# main3.net
KiCad netlist of a schematic drawn in EAGLE
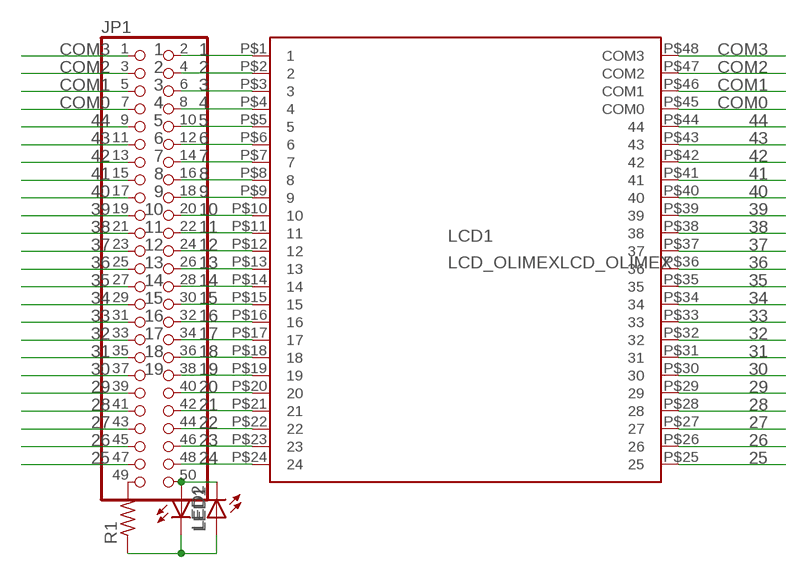
[diagram p0: schematic, sheet 1]

(export (version "E")
  (design (tool "Eeschema 10.0.6"))
  (components
    (comp (ref "JP1")
      (value "PINHD-2X25")
      (footprint "eagle-import:2X25")
      (libsource (lib "eagle-import") (part "PINHD-2X25"))
    )
    (comp (ref "LCD1")
      (value "LCD_OLIMEXLCD_OLIMEX")
      (footprint "eagle-import:LCD_OLIMEX")
      (libsource (lib "eagle-import") (part "LCD_OLIMEXLCD_OLIMEX"))
    )
    (comp (ref "LED1")
      (value "LED_ESML0603")
      (footprint "eagle-import:LED_SML0603")
      (libsource (lib "eagle-import") (part "LED_ESML0603"))
    )
    (comp (ref "LED2")
      (value "LED_ESML0603")
      (footprint "eagle-import:LED_SML0603")
      (libsource (lib "eagle-import") (part "LED_ESML0603"))
    )
    (comp (ref "R1")
      (value "R-US_R0603")
      (footprint "eagle-import:R0603")
      (libsource (lib "eagle-import") (part "R-US_R0603"))
    )
  )
  (nets
    (net (code "1") (name "/1") (class "Default")
      (node (ref "JP1") (pin "2") (pinfunction "2_2") (pintype "passive"))
      (node (ref "LCD1") (pin "P$1") (pinfunction "1_P$1") (pintype "bidirectional"))
    )
    (net (code "2") (name "/2") (class "Default")
      (node (ref "JP1") (pin "4") (pinfunction "4_4") (pintype "passive"))
      (node (ref "LCD1") (pin "P$2") (pinfunction "2_P$2") (pintype "bidirectional"))
    )
    (net (code "3") (name "/3") (class "Default")
      (node (ref "JP1") (pin "6") (pinfunction "6_6") (pintype "passive"))
      (node (ref "LCD1") (pin "P$3") (pinfunction "3_P$3") (pintype "bidirectional"))
    )
    (net (code "4") (name "/4") (class "Default")
      (node (ref "JP1") (pin "8") (pinfunction "8_8") (pintype "passive"))
      (node (ref "LCD1") (pin "P$4") (pinfunction "4_P$4") (pintype "bidirectional"))
    )
    (net (code "5") (name "/5") (class "Default")
      (node (ref "JP1") (pin "10") (pinfunction "10_10") (pintype "passive"))
      (node (ref "LCD1") (pin "P$5") (pinfunction "5_P$5") (pintype "bidirectional"))
    )
    (net (code "6") (name "/6") (class "Default")
      (node (ref "JP1") (pin "12") (pinfunction "12_12") (pintype "passive"))
      (node (ref "LCD1") (pin "P$6") (pinfunction "6_P$6") (pintype "bidirectional"))
    )
    (net (code "7") (name "/7") (class "Default")
      (node (ref "JP1") (pin "14") (pinfunction "14_14") (pintype "passive"))
      (node (ref "LCD1") (pin "P$7") (pinfunction "7_P$7") (pintype "bidirectional"))
    )
    (net (code "8") (name "/8") (class "Default")
      (node (ref "JP1") (pin "16") (pinfunction "16_16") (pintype "passive"))
      (node (ref "LCD1") (pin "P$8") (pinfunction "8_P$8") (pintype "bidirectional"))
    )
    (net (code "9") (name "/9") (class "Default")
      (node (ref "JP1") (pin "18") (pinfunction "18_18") (pintype "passive"))
      (node (ref "LCD1") (pin "P$9") (pinfunction "9_P$9") (pintype "bidirectional"))
    )
    (net (code "10") (name "/10") (class "Default")
      (node (ref "JP1") (pin "20") (pinfunction "20_20") (pintype "passive"))
      (node (ref "LCD1") (pin "P$10") (pinfunction "10_P$10") (pintype "bidirectional"))
    )
    (net (code "11") (name "/11") (class "Default")
      (node (ref "JP1") (pin "22") (pinfunction "22_22") (pintype "passive"))
      (node (ref "LCD1") (pin "P$11") (pinfunction "11_P$11") (pintype "bidirectional"))
    )
    (net (code "12") (name "/12") (class "Default")
      (node (ref "JP1") (pin "24") (pinfunction "24_24") (pintype "passive"))
      (node (ref "LCD1") (pin "P$12") (pinfunction "12_P$12") (pintype "bidirectional"))
    )
    (net (code "13") (name "/13") (class "Default")
      (node (ref "JP1") (pin "26") (pinfunction "26_26") (pintype "passive"))
      (node (ref "LCD1") (pin "P$13") (pinfunction "13_P$13") (pintype "bidirectional"))
    )
    (net (code "14") (name "/14") (class "Default")
      (node (ref "JP1") (pin "28") (pinfunction "28_28") (pintype "passive"))
      (node (ref "LCD1") (pin "P$14") (pinfunction "14_P$14") (pintype "bidirectional"))
    )
    (net (code "15") (name "/15") (class "Default")
      (node (ref "JP1") (pin "30") (pinfunction "30_30") (pintype "passive"))
      (node (ref "LCD1") (pin "P$15") (pinfunction "15_P$15") (pintype "bidirectional"))
    )
    (net (code "16") (name "/16") (class "Default")
      (node (ref "JP1") (pin "32") (pinfunction "32_32") (pintype "passive"))
      (node (ref "LCD1") (pin "P$16") (pinfunction "16_P$16") (pintype "bidirectional"))
    )
    (net (code "17") (name "/17") (class "Default")
      (node (ref "JP1") (pin "34") (pinfunction "34_34") (pintype "passive"))
      (node (ref "LCD1") (pin "P$17") (pinfunction "17_P$17") (pintype "bidirectional"))
    )
    (net (code "18") (name "/18") (class "Default")
      (node (ref "JP1") (pin "36") (pinfunction "36_36") (pintype "passive"))
      (node (ref "LCD1") (pin "P$18") (pinfunction "18_P$18") (pintype "bidirectional"))
    )
    (net (code "19") (name "/19") (class "Default")
      (node (ref "JP1") (pin "38") (pinfunction "38_38") (pintype "passive"))
      (node (ref "LCD1") (pin "P$19") (pinfunction "19_P$19") (pintype "bidirectional"))
    )
    (net (code "20") (name "/20") (class "Default")
      (node (ref "JP1") (pin "40") (pinfunction "40_40") (pintype "passive"))
      (node (ref "LCD1") (pin "P$20") (pinfunction "20_P$20") (pintype "bidirectional"))
    )
    (net (code "21") (name "/21") (class "Default")
      (node (ref "JP1") (pin "42") (pinfunction "42_42") (pintype "passive"))
      (node (ref "LCD1") (pin "P$21") (pinfunction "21_P$21") (pintype "bidirectional"))
    )
    (net (code "22") (name "/22") (class "Default")
      (node (ref "JP1") (pin "44") (pinfunction "44_44") (pintype "passive"))
      (node (ref "LCD1") (pin "P$22") (pinfunction "22_P$22") (pintype "bidirectional"))
    )
    (net (code "23") (name "/23") (class "Default")
      (node (ref "JP1") (pin "46") (pinfunction "46_46") (pintype "passive"))
      (node (ref "LCD1") (pin "P$23") (pinfunction "23_P$23") (pintype "bidirectional"))
    )
    (net (code "24") (name "/24") (class "Default")
      (node (ref "JP1") (pin "48") (pinfunction "48_48") (pintype "passive"))
      (node (ref "LCD1") (pin "P$24") (pinfunction "24_P$24") (pintype "bidirectional"))
    )
    (net (code "25") (name "/25") (class "Default")
      (node (ref "JP1") (pin "47") (pinfunction "47_47") (pintype "passive"))
      (node (ref "LCD1") (pin "P$25") (pinfunction "25_P$25") (pintype "bidirectional"))
    )
    (net (code "26") (name "/26") (class "Default")
      (node (ref "JP1") (pin "45") (pinfunction "45_45") (pintype "passive"))
      (node (ref "LCD1") (pin "P$26") (pinfunction "26_P$26") (pintype "bidirectional"))
    )
    (net (code "27") (name "/27") (class "Default")
      (node (ref "JP1") (pin "43") (pinfunction "43_43") (pintype "passive"))
      (node (ref "LCD1") (pin "P$27") (pinfunction "27_P$27") (pintype "bidirectional"))
    )
    (net (code "28") (name "/28") (class "Default")
      (node (ref "JP1") (pin "41") (pinfunction "41_41") (pintype "passive"))
      (node (ref "LCD1") (pin "P$28") (pinfunction "28_P$28") (pintype "bidirectional"))
    )
    (net (code "29") (name "/29") (class "Default")
      (node (ref "JP1") (pin "39") (pinfunction "39_39") (pintype "passive"))
      (node (ref "LCD1") (pin "P$29") (pinfunction "29_P$29") (pintype "bidirectional"))
    )
    (net (code "30") (name "/30") (class "Default")
      (node (ref "JP1") (pin "37") (pinfunction "37_37") (pintype "passive"))
      (node (ref "LCD1") (pin "P$30") (pinfunction "30_P$30") (pintype "bidirectional"))
    )
    (net (code "31") (name "/31") (class "Default")
      (node (ref "JP1") (pin "35") (pinfunction "35_35") (pintype "passive"))
      (node (ref "LCD1") (pin "P$31") (pinfunction "31_P$31") (pintype "bidirectional"))
    )
    (net (code "32") (name "/32") (class "Default")
      (node (ref "JP1") (pin "33") (pinfunction "33_33") (pintype "passive"))
      (node (ref "LCD1") (pin "P$32") (pinfunction "32_P$32") (pintype "bidirectional"))
    )
    (net (code "33") (name "/33") (class "Default")
      (node (ref "JP1") (pin "31") (pinfunction "31_31") (pintype "passive"))
      (node (ref "LCD1") (pin "P$33") (pinfunction "33_P$33") (pintype "bidirectional"))
    )
    (net (code "34") (name "/34") (class "Default")
      (node (ref "JP1") (pin "29") (pinfunction "29_29") (pintype "passive"))
      (node (ref "LCD1") (pin "P$34") (pinfunction "34_P$34") (pintype "bidirectional"))
    )
    (net (code "35") (name "/35") (class "Default")
      (node (ref "JP1") (pin "27") (pinfunction "27_27") (pintype "passive"))
      (node (ref "LCD1") (pin "P$35") (pinfunction "35_P$35") (pintype "bidirectional"))
    )
    (net (code "36") (name "/36") (class "Default")
      (node (ref "JP1") (pin "25") (pinfunction "25_25") (pintype "passive"))
      (node (ref "LCD1") (pin "P$36") (pinfunction "36_P$36") (pintype "bidirectional"))
    )
    (net (code "37") (name "/37") (class "Default")
      (node (ref "JP1") (pin "23") (pinfunction "23_23") (pintype "passive"))
      (node (ref "LCD1") (pin "P$37") (pinfunction "37_P$37") (pintype "bidirectional"))
    )
    (net (code "38") (name "/38") (class "Default")
      (node (ref "JP1") (pin "21") (pinfunction "21_21") (pintype "passive"))
      (node (ref "LCD1") (pin "P$38") (pinfunction "38_P$38") (pintype "bidirectional"))
    )
    (net (code "39") (name "/39") (class "Default")
      (node (ref "JP1") (pin "19") (pinfunction "19_19") (pintype "passive"))
      (node (ref "LCD1") (pin "P$39") (pinfunction "39_P$39") (pintype "bidirectional"))
    )
    (net (code "40") (name "/40") (class "Default")
      (node (ref "JP1") (pin "17") (pinfunction "17_17") (pintype "passive"))
      (node (ref "LCD1") (pin "P$40") (pinfunction "40_P$40") (pintype "bidirectional"))
    )
    (net (code "41") (name "/41") (class "Default")
      (node (ref "JP1") (pin "15") (pinfunction "15_15") (pintype "passive"))
      (node (ref "LCD1") (pin "P$41") (pinfunction "41_P$41") (pintype "bidirectional"))
    )
    (net (code "42") (name "/42") (class "Default")
      (node (ref "JP1") (pin "13") (pinfunction "13_13") (pintype "passive"))
      (node (ref "LCD1") (pin "P$42") (pinfunction "42_P$42") (pintype "bidirectional"))
    )
    (net (code "43") (name "/43") (class "Default")
      (node (ref "JP1") (pin "11") (pinfunction "11_11") (pintype "passive"))
      (node (ref "LCD1") (pin "P$43") (pinfunction "43_P$43") (pintype "bidirectional"))
    )
    (net (code "44") (name "/44") (class "Default")
      (node (ref "JP1") (pin "9") (pinfunction "9_9") (pintype "passive"))
      (node (ref "LCD1") (pin "P$44") (pinfunction "44_P$44") (pintype "bidirectional"))
    )
    (net (code "45") (name "/COM0") (class "Default")
      (node (ref "JP1") (pin "7") (pinfunction "7_7") (pintype "passive"))
      (node (ref "LCD1") (pin "P$45") (pinfunction "COM0_P$45") (pintype "bidirectional"))
    )
    (net (code "46") (name "/COM1") (class "Default")
      (node (ref "JP1") (pin "5") (pinfunction "5_5") (pintype "passive"))
      (node (ref "LCD1") (pin "P$46") (pinfunction "COM1_P$46") (pintype "bidirectional"))
    )
    (net (code "47") (name "/COM2") (class "Default")
      (node (ref "JP1") (pin "3") (pinfunction "3_3") (pintype "passive"))
      (node (ref "LCD1") (pin "P$47") (pinfunction "COM2_P$47") (pintype "bidirectional"))
    )
    (net (code "48") (name "/COM3") (class "Default")
      (node (ref "JP1") (pin "1") (pinfunction "1_1") (pintype "passive"))
      (node (ref "LCD1") (pin "P$48") (pinfunction "COM3_P$48") (pintype "bidirectional"))
    )
    (net (code "49") (name "Net-(JP1-Pad49)") (class "Default")
      (node (ref "JP1") (pin "49") (pinfunction "49_49") (pintype "passive"))
      (node (ref "R1") (pin "2") (pinfunction "2_2") (pintype "passive"))
    )
    (net (code "50") (name "Net-(JP1-Pad50)") (class "Default")
      (node (ref "JP1") (pin "50") (pinfunction "50_50") (pintype "passive"))
      (node (ref "LED1") (pin "A") (pinfunction "A_A") (pintype "passive"))
      (node (ref "LED2") (pin "C") (pinfunction "C_C") (pintype "passive"))
    )
    (net (code "51") (name "Net-(LED1-PadC)") (class "Default")
      (node (ref "LED1") (pin "C") (pinfunction "C_C") (pintype "passive"))
      (node (ref "LED2") (pin "A") (pinfunction "A_A") (pintype "passive"))
      (node (ref "R1") (pin "1") (pinfunction "1_1") (pintype "passive"))
    )
  )
)
